# invader_asyn_node.net
KiCad netlist of a schematic drawn in EAGLE
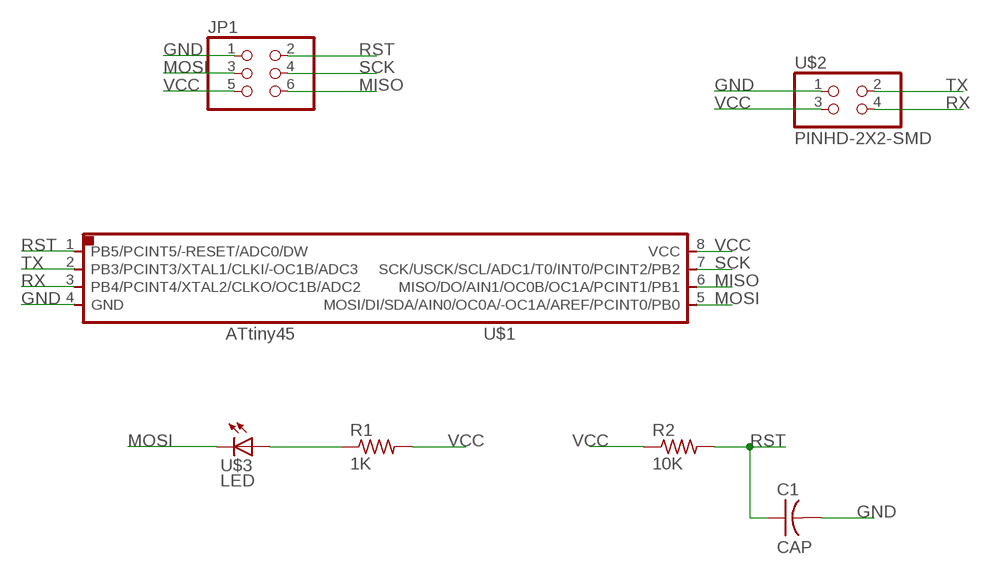
[diagram p0: schematic, sheet 1]

(export (version "E")
  (design (tool "Eeschema 10.0.6"))
  (components
    (comp (ref "C1")
      (value "CAP")
      (footprint "eagle-import:C1206FAB")
      (libsource (lib "eagle-import") (part "CAP-US1206FAB"))
    )
    (comp (ref "JP1")
      (value "PINHD-2X3-SMD")
      (footprint "eagle-import:2X03SMD")
      (libsource (lib "eagle-import") (part "PINHD-2X3-SMD"))
    )
    (comp (ref "R1")
      (value "1K")
      (footprint "eagle-import:R1206")
      (libsource (lib "eagle-import") (part "RES-US1206"))
    )
    (comp (ref "R2")
      (value "10K")
      (footprint "eagle-import:R1206")
      (libsource (lib "eagle-import") (part "RES-US1206"))
    )
    (comp (ref "U$1")
      (value "ATTINY45SI")
      (footprint "eagle-import:SOIC8")
      (libsource (lib "eagle-import") (part "ATTINY45SI"))
    )
    (comp (ref "U$2")
      (value "PINHD-2X2-SMD")
      (footprint "eagle-import:2X02SMD")
      (libsource (lib "eagle-import") (part "PINHD-2X2-SMD"))
    )
    (comp (ref "U$3")
      (value "LED")
      (footprint "eagle-import:LED1206FAB")
      (libsource (lib "eagle-import") (part "LEDFAB1206"))
    )
  )
  (nets
    (net (code "1") (name "/GND") (class "Default")
      (node (ref "C1") (pin "2") (pinfunction "2_2") (pintype "passive"))
      (node (ref "JP1") (pin "1") (pinfunction "1_1") (pintype "passive"))
      (node (ref "U$1") (pin "4") (pinfunction "GND_4") (pintype "bidirectional"))
      (node (ref "U$2") (pin "1") (pinfunction "1_1") (pintype "passive"))
    )
    (net (code "2") (name "/MISO") (class "Default")
      (node (ref "JP1") (pin "6") (pinfunction "6_6") (pintype "passive"))
      (node (ref "U$1") (pin "6") (pinfunction "MISO/DO/AIN1/OC0B/OC1A/PCINT1/PB1_6") (pintype "bidirectional"))
    )
    (net (code "3") (name "/MOSI") (class "Default")
      (node (ref "JP1") (pin "3") (pinfunction "3_3") (pintype "passive"))
      (node (ref "U$1") (pin "5") (pinfunction "MOSI/DI/SDA/AIN0/OC0A/-OC1A/AREF/PCINT0/PB0_5") (pintype "bidirectional"))
      (node (ref "U$3") (pin "2") (pinfunction "C_2") (pintype "passive"))
    )
    (net (code "4") (name "/RST") (class "Default")
      (node (ref "C1") (pin "1") (pinfunction "1_1") (pintype "passive"))
      (node (ref "JP1") (pin "2") (pinfunction "2_2") (pintype "passive"))
      (node (ref "R2") (pin "2") (pinfunction "2_2") (pintype "passive"))
      (node (ref "U$1") (pin "1") (pinfunction "PB5/PCINT5/-RESET/ADC0/DW_1") (pintype "bidirectional"))
    )
    (net (code "5") (name "/RX") (class "Default")
      (node (ref "U$1") (pin "3") (pinfunction "PB4/PCINT4/XTAL2/CLKO/OC1B/ADC2_3") (pintype "bidirectional"))
      (node (ref "U$2") (pin "4") (pinfunction "4_4") (pintype "passive"))
    )
    (net (code "6") (name "/SCK") (class "Default")
      (node (ref "JP1") (pin "4") (pinfunction "4_4") (pintype "passive"))
      (node (ref "U$1") (pin "7") (pinfunction "SCK/USCK/SCL/ADC1/T0/INT0/PCINT2/PB2_7") (pintype "bidirectional"))
    )
    (net (code "7") (name "/TX") (class "Default")
      (node (ref "U$1") (pin "2") (pinfunction "PB3/PCINT3/XTAL1/CLKI/-OC1B/ADC3_2") (pintype "bidirectional"))
      (node (ref "U$2") (pin "2") (pinfunction "2_2") (pintype "passive"))
    )
    (net (code "8") (name "/VCC") (class "Default")
      (node (ref "JP1") (pin "5") (pinfunction "5_5") (pintype "passive"))
      (node (ref "R1") (pin "2") (pinfunction "2_2") (pintype "passive"))
      (node (ref "R2") (pin "1") (pinfunction "1_1") (pintype "passive"))
      (node (ref "U$1") (pin "8") (pinfunction "VCC_8") (pintype "bidirectional"))
      (node (ref "U$2") (pin "3") (pinfunction "3_3") (pintype "passive"))
    )
    (net (code "9") (name "Net-(U$3-A)") (class "Default")
      (node (ref "R1") (pin "1") (pinfunction "1_1") (pintype "passive"))
      (node (ref "U$3") (pin "1") (pinfunction "A_1") (pintype "passive"))
    )
  )
)
